# ADS1299.net
KiCad netlist of a schematic drawn in Altium Designer
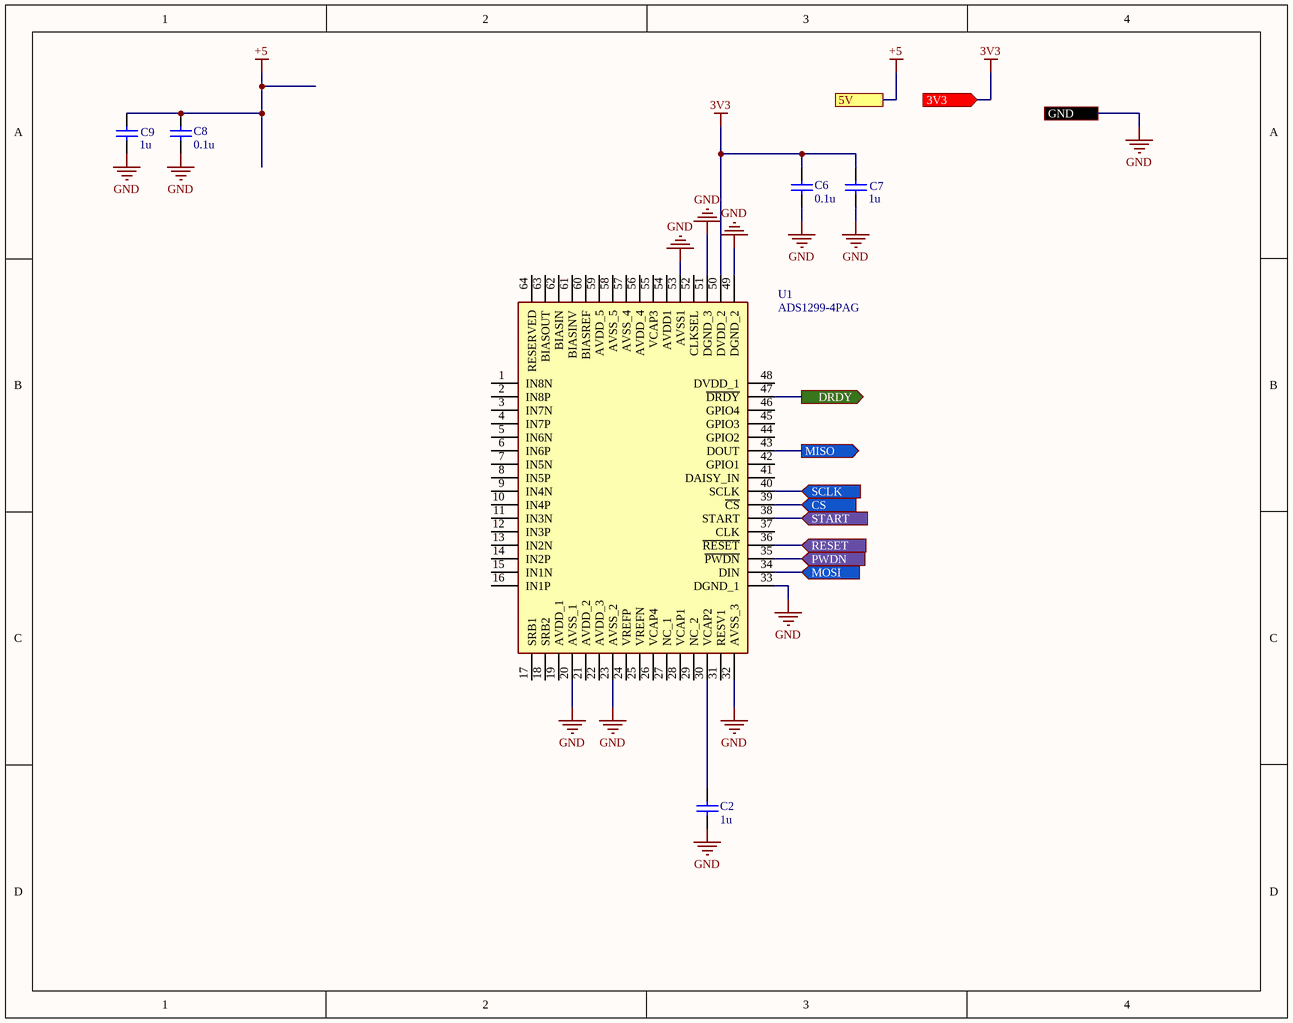
[diagram p0: ADS1299.SchDoc]

(export (version "E")
  (design (tool "Eeschema 10.0.6"))
  (components
    (comp (ref "C2")
      (value "1u")
      (description "Capacitor")
      (libsource (lib "Simulation Generic Components") (part "Capacitor"))
    )
    (comp (ref "C6")
      (value "0.1u")
      (description "Capacitor")
      (libsource (lib "Simulation Generic Components") (part "Capacitor"))
    )
    (comp (ref "C7")
      (value "1u")
      (description "Capacitor")
      (libsource (lib "Simulation Generic Components") (part "Capacitor"))
    )
    (comp (ref "C8")
      (value "0.1u")
      (description "Capacitor")
      (libsource (lib "Simulation Generic Components") (part "Capacitor"))
    )
    (comp (ref "C9")
      (value "1u")
      (description "Capacitor")
      (libsource (lib "Simulation Generic Components") (part "Capacitor"))
    )
    (comp (ref "U1")
      (value "ADS1299-4PAG")
      (footprint "QFP50P1200X1200X120-64N")
      (description "Low-Noise, 4-Channel, 24-Bit Analog-to-Digital Converter for Biopotential Measurements")
      (fields (field (name "MOUSER PART NUMBER") "595-ADS1299-4PAG"))
      (libsource (lib "ADS1299-4PAG") (part "ADS1299-4PAG"))
    )
  )
  (nets
    (net (code "1") (name "+5") (class "Default")
      (node (ref "C8") (pin "2") (pinfunction "2_2") (pintype "passive"))
      (node (ref "C9") (pin "2") (pinfunction "2_2") (pintype "passive"))
    )
    (net (code "2") (name "/CS") (class "Default")
      (node (ref "U1") (pin "39") (pinfunction "~{CS}_39") (pintype "passive"))
    )
    (net (code "3") (name "/DRDY") (class "Default")
      (node (ref "U1") (pin "47") (pinfunction "~{DRDY}_47") (pintype "passive"))
    )
    (net (code "4") (name "/MISO") (class "Default")
      (node (ref "U1") (pin "43") (pinfunction "DOUT_43") (pintype "passive"))
    )
    (net (code "5") (name "/MOSI") (class "Default")
      (node (ref "U1") (pin "34") (pinfunction "DIN_34") (pintype "passive"))
    )
    (net (code "6") (name "/PWDN") (class "Default")
      (node (ref "U1") (pin "35") (pinfunction "~{PWDN}_35") (pintype "passive"))
    )
    (net (code "7") (name "/RESET") (class "Default")
      (node (ref "U1") (pin "36") (pinfunction "~{RESET}_36") (pintype "passive"))
    )
    (net (code "8") (name "/SCLK") (class "Default")
      (node (ref "U1") (pin "40") (pinfunction "SCLK_40") (pintype "passive"))
    )
    (net (code "9") (name "/START") (class "Default")
      (node (ref "U1") (pin "38") (pinfunction "START_38") (pintype "passive"))
    )
    (net (code "10") (name "3V3") (class "Default")
      (node (ref "C6") (pin "2") (pinfunction "2_2") (pintype "passive"))
      (node (ref "C7") (pin "2") (pinfunction "2_2") (pintype "passive"))
      (node (ref "U1") (pin "50") (pinfunction "DVDD_2_50") (pintype "passive"))
    )
    (net (code "11") (name "GND") (class "Default")
      (node (ref "C2") (pin "2") (pinfunction "2_2") (pintype "passive"))
      (node (ref "C6") (pin "1") (pinfunction "1_1") (pintype "passive"))
      (node (ref "C7") (pin "1") (pinfunction "1_1") (pintype "passive"))
      (node (ref "C8") (pin "1") (pinfunction "1_1") (pintype "passive"))
      (node (ref "C9") (pin "1") (pinfunction "1_1") (pintype "passive"))
      (node (ref "U1") (pin "20") (pinfunction "AVSS_1_20") (pintype "passive"))
      (node (ref "U1") (pin "23") (pinfunction "AVSS_2_23") (pintype "passive"))
      (node (ref "U1") (pin "32") (pinfunction "AVSS_3_32") (pintype "passive"))
      (node (ref "U1") (pin "33") (pinfunction "DGND_1_33") (pintype "passive"))
      (node (ref "U1") (pin "49") (pinfunction "DGND_2_49") (pintype "passive"))
      (node (ref "U1") (pin "51") (pinfunction "DGND_3_51") (pintype "passive"))
      (node (ref "U1") (pin "53") (pinfunction "AVSS1_53") (pintype "passive"))
    )
    (net (code "12") (name "Net-(U1-VCAP2)") (class "Default")
      (node (ref "C2") (pin "1") (pinfunction "1_1") (pintype "passive"))
      (node (ref "U1") (pin "30") (pinfunction "VCAP2_30") (pintype "passive"))
    )
    (net (code "13") (name "unconnected-(U1-AVDD1-Pad54)") (class "Default")
      (node (ref "U1") (pin "54") (pinfunction "AVDD1_54") (pintype "passive"))
    )
    (net (code "14") (name "unconnected-(U1-AVDD_1-Pad19)") (class "Default")
      (node (ref "U1") (pin "19") (pinfunction "AVDD_1_19") (pintype "passive"))
    )
    (net (code "15") (name "unconnected-(U1-AVDD_2-Pad21)") (class "Default")
      (node (ref "U1") (pin "21") (pinfunction "AVDD_2_21") (pintype "passive"))
    )
    (net (code "16") (name "unconnected-(U1-AVDD_3-Pad22)") (class "Default")
      (node (ref "U1") (pin "22") (pinfunction "AVDD_3_22") (pintype "passive"))
    )
    (net (code "17") (name "unconnected-(U1-AVDD_4-Pad56)") (class "Default")
      (node (ref "U1") (pin "56") (pinfunction "AVDD_4_56") (pintype "passive"))
    )
    (net (code "18") (name "unconnected-(U1-AVDD_5-Pad59)") (class "Default")
      (node (ref "U1") (pin "59") (pinfunction "AVDD_5_59") (pintype "passive"))
    )
    (net (code "19") (name "unconnected-(U1-AVSS_4-Pad57)") (class "Default")
      (node (ref "U1") (pin "57") (pinfunction "AVSS_4_57") (pintype "passive"))
    )
    (net (code "20") (name "unconnected-(U1-AVSS_5-Pad58)") (class "Default")
      (node (ref "U1") (pin "58") (pinfunction "AVSS_5_58") (pintype "passive"))
    )
    (net (code "21") (name "unconnected-(U1-BIASIN-Pad62)") (class "Default")
      (node (ref "U1") (pin "62") (pinfunction "BIASIN_62") (pintype "passive"))
    )
    (net (code "22") (name "unconnected-(U1-BIASINV-Pad61)") (class "Default")
      (node (ref "U1") (pin "61") (pinfunction "BIASINV_61") (pintype "passive"))
    )
    (net (code "23") (name "unconnected-(U1-BIASOUT-Pad63)") (class "Default")
      (node (ref "U1") (pin "63") (pinfunction "BIASOUT_63") (pintype "passive"))
    )
    (net (code "24") (name "unconnected-(U1-BIASREF-Pad60)") (class "Default")
      (node (ref "U1") (pin "60") (pinfunction "BIASREF_60") (pintype "passive"))
    )
    (net (code "25") (name "unconnected-(U1-CLK-Pad37)") (class "Default")
      (node (ref "U1") (pin "37") (pinfunction "CLK_37") (pintype "passive"))
    )
    (net (code "26") (name "unconnected-(U1-CLKSEL-Pad52)") (class "Default")
      (node (ref "U1") (pin "52") (pinfunction "CLKSEL_52") (pintype "passive"))
    )
    (net (code "27") (name "unconnected-(U1-DAISY_IN-Pad41)") (class "Default")
      (node (ref "U1") (pin "41") (pinfunction "DAISY_IN_41") (pintype "passive"))
    )
    (net (code "28") (name "unconnected-(U1-DVDD_1-Pad48)") (class "Default")
      (node (ref "U1") (pin "48") (pinfunction "DVDD_1_48") (pintype "passive"))
    )
    (net (code "29") (name "unconnected-(U1-GPIO1-Pad42)") (class "Default")
      (node (ref "U1") (pin "42") (pinfunction "GPIO1_42") (pintype "passive"))
    )
    (net (code "30") (name "unconnected-(U1-GPIO2-Pad44)") (class "Default")
      (node (ref "U1") (pin "44") (pinfunction "GPIO2_44") (pintype "passive"))
    )
    (net (code "31") (name "unconnected-(U1-GPIO3-Pad45)") (class "Default")
      (node (ref "U1") (pin "45") (pinfunction "GPIO3_45") (pintype "passive"))
    )
    (net (code "32") (name "unconnected-(U1-GPIO4-Pad46)") (class "Default")
      (node (ref "U1") (pin "46") (pinfunction "GPIO4_46") (pintype "passive"))
    )
    (net (code "33") (name "unconnected-(U1-IN1N-Pad15)") (class "Default")
      (node (ref "U1") (pin "15") (pinfunction "IN1N_15") (pintype "passive"))
    )
    (net (code "34") (name "unconnected-(U1-IN1P-Pad16)") (class "Default")
      (node (ref "U1") (pin "16") (pinfunction "IN1P_16") (pintype "passive"))
    )
    (net (code "35") (name "unconnected-(U1-IN2N-Pad13)") (class "Default")
      (node (ref "U1") (pin "13") (pinfunction "IN2N_13") (pintype "passive"))
    )
    (net (code "36") (name "unconnected-(U1-IN2P-Pad14)") (class "Default")
      (node (ref "U1") (pin "14") (pinfunction "IN2P_14") (pintype "passive"))
    )
    (net (code "37") (name "unconnected-(U1-IN3N-Pad11)") (class "Default")
      (node (ref "U1") (pin "11") (pinfunction "IN3N_11") (pintype "passive"))
    )
    (net (code "38") (name "unconnected-(U1-IN3P-Pad12)") (class "Default")
      (node (ref "U1") (pin "12") (pinfunction "IN3P_12") (pintype "passive"))
    )
    (net (code "39") (name "unconnected-(U1-IN4N-Pad9)") (class "Default")
      (node (ref "U1") (pin "9") (pinfunction "IN4N_9") (pintype "passive"))
    )
    (net (code "40") (name "unconnected-(U1-IN4P-Pad10)") (class "Default")
      (node (ref "U1") (pin "10") (pinfunction "IN4P_10") (pintype "passive"))
    )
    (net (code "41") (name "unconnected-(U1-IN5N-Pad7)") (class "Default")
      (node (ref "U1") (pin "7") (pinfunction "IN5N_7") (pintype "passive"))
    )
    (net (code "42") (name "unconnected-(U1-IN5P-Pad8)") (class "Default")
      (node (ref "U1") (pin "8") (pinfunction "IN5P_8") (pintype "passive"))
    )
    (net (code "43") (name "unconnected-(U1-IN6N-Pad5)") (class "Default")
      (node (ref "U1") (pin "5") (pinfunction "IN6N_5") (pintype "passive"))
    )
    (net (code "44") (name "unconnected-(U1-IN6P-Pad6)") (class "Default")
      (node (ref "U1") (pin "6") (pinfunction "IN6P_6") (pintype "passive"))
    )
    (net (code "45") (name "unconnected-(U1-IN7N-Pad3)") (class "Default")
      (node (ref "U1") (pin "3") (pinfunction "IN7N_3") (pintype "passive"))
    )
    (net (code "46") (name "unconnected-(U1-IN7P-Pad4)") (class "Default")
      (node (ref "U1") (pin "4") (pinfunction "IN7P_4") (pintype "passive"))
    )
    (net (code "47") (name "unconnected-(U1-IN8N-Pad1)") (class "Default")
      (node (ref "U1") (pin "1") (pinfunction "IN8N_1") (pintype "passive"))
    )
    (net (code "48") (name "unconnected-(U1-IN8P-Pad2)") (class "Default")
      (node (ref "U1") (pin "2") (pinfunction "IN8P_2") (pintype "passive"))
    )
    (net (code "49") (name "unconnected-(U1-NC_1-Pad27)") (class "Default")
      (node (ref "U1") (pin "27") (pinfunction "NC_1_27") (pintype "passive"))
    )
    (net (code "50") (name "unconnected-(U1-NC_2-Pad29)") (class "Default")
      (node (ref "U1") (pin "29") (pinfunction "NC_2_29") (pintype "passive"))
    )
    (net (code "51") (name "unconnected-(U1-RESERVED-Pad64)") (class "Default")
      (node (ref "U1") (pin "64") (pinfunction "RESERVED_64") (pintype "passive"))
    )
    (net (code "52") (name "unconnected-(U1-RESV1-Pad31)") (class "Default")
      (node (ref "U1") (pin "31") (pinfunction "RESV1_31") (pintype "passive"))
    )
    (net (code "53") (name "unconnected-(U1-SRB1-Pad17)") (class "Default")
      (node (ref "U1") (pin "17") (pinfunction "SRB1_17") (pintype "passive"))
    )
    (net (code "54") (name "unconnected-(U1-SRB2-Pad18)") (class "Default")
      (node (ref "U1") (pin "18") (pinfunction "SRB2_18") (pintype "passive"))
    )
    (net (code "55") (name "unconnected-(U1-VCAP1-Pad28)") (class "Default")
      (node (ref "U1") (pin "28") (pinfunction "VCAP1_28") (pintype "passive"))
    )
    (net (code "56") (name "unconnected-(U1-VCAP3-Pad55)") (class "Default")
      (node (ref "U1") (pin "55") (pinfunction "VCAP3_55") (pintype "passive"))
    )
    (net (code "57") (name "unconnected-(U1-VCAP4-Pad26)") (class "Default")
      (node (ref "U1") (pin "26") (pinfunction "VCAP4_26") (pintype "passive"))
    )
    (net (code "58") (name "unconnected-(U1-VREFN-Pad25)") (class "Default")
      (node (ref "U1") (pin "25") (pinfunction "VREFN_25") (pintype "passive"))
    )
    (net (code "59") (name "unconnected-(U1-VREFP-Pad24)") (class "Default")
      (node (ref "U1") (pin "24") (pinfunction "VREFP_24") (pintype "passive"))
    )
  )
)
